# Sheet1.net
KiCad netlist of a schematic drawn in Altium Designer
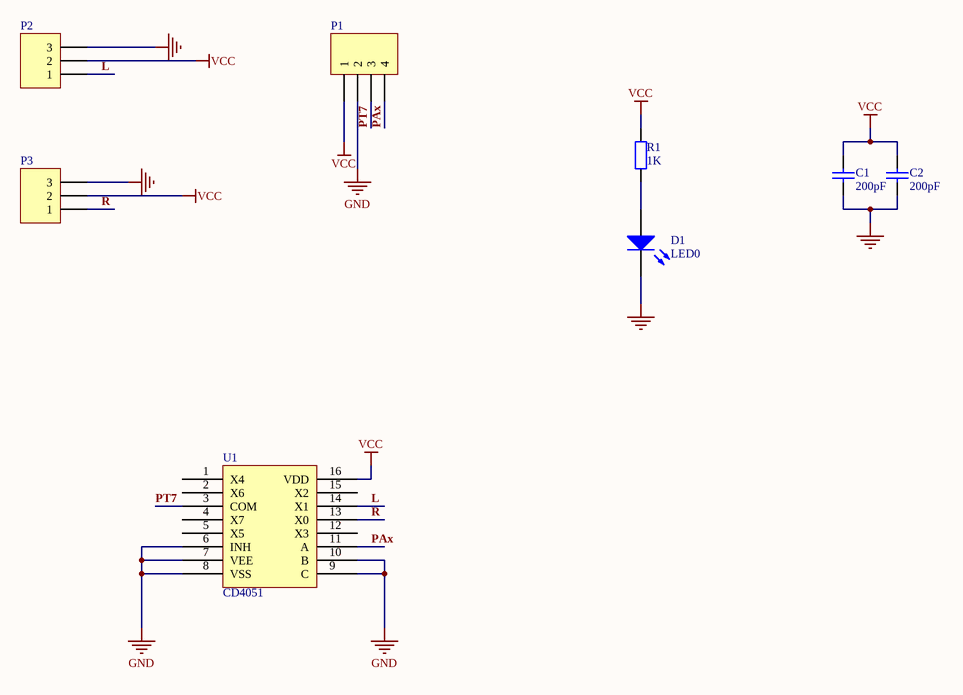
[diagram p0: Sheet1.SchDoc]

(export (version "E")
  (design (tool "Eeschema 10.0.6"))
  (components
    (comp (ref "C1")
      (value "200pF")
      (footprint "C0805")
      (description "Capacitor")
      (fields (field (name "Comment") "Cap") (field (name "PUBLISHER") "Altium Limited"))
      (libsource (lib "Miscellaneous Devices") (part "Cap"))
    )
    (comp (ref "C2")
      (value "200pF")
      (footprint "C0805")
      (description "Capacitor")
      (fields (field (name "Comment") "Cap") (field (name "PUBLISHER") "Altium Limited"))
      (libsource (lib "Miscellaneous Devices") (part "Cap"))
    )
    (comp (ref "D1")
      (value "LED0")
      (footprint "C0805")
      (description "Typical INFRARED GaAs LED")
      (fields (field (name "PUBLISHER") "Altium Limited"))
      (libsource (lib "Miscellaneous Devices") (part "LED0"))
    )
    (comp (ref "P1")
      (value "Header 4")
      (footprint "HDR1X4")
      (description "Header, 4-Pin")
      (fields (field (name "PUBLISHER") "Altium Limited"))
      (libsource (lib "Miscellaneous Connectors") (part "Header 4"))
    )
    (comp (ref "P2")
      (value "Header 3")
      (footprint "HDR1X3")
      (description "Header, 3-Pin")
      (fields (field (name "PUBLISHER") "Altium Limited"))
      (libsource (lib "Miscellaneous Connectors") (part "Header 3"))
    )
    (comp (ref "P3")
      (value "Header 3")
      (footprint "HDR1X3")
      (description "Header, 3-Pin")
      (fields (field (name "PUBLISHER") "Altium Limited"))
      (libsource (lib "Miscellaneous Connectors") (part "Header 3"))
    )
    (comp (ref "R1")
      (value "1K")
      (footprint "C0805")
      (description "Resistor")
      (fields (field (name "Comment") "Res2") (field (name "PUBLISHER") "Altium Limited"))
      (libsource (lib "Miscellaneous Devices") (part "Res2"))
    )
    (comp (ref "U1") (value "CD4051") (footprint "DIP-16") (libsource (lib "Schlib1") (part "Component_1")))
  )
  (nets
    (net (code "1") (name "/L") (class "Default")
      (node (ref "P2") (pin "1") (pinfunction "1_1") (pintype "passive"))
      (node (ref "U1") (pin "14") (pinfunction "X1_14") (pintype "passive"))
    )
    (net (code "2") (name "/PAx") (class "Default")
      (node (ref "P1") (pin "4") (pinfunction "4_4") (pintype "passive"))
      (node (ref "U1") (pin "11") (pinfunction "A_11") (pintype "passive"))
    )
    (net (code "3") (name "/PT7") (class "Default")
      (node (ref "P1") (pin "3") (pinfunction "3_3") (pintype "passive"))
      (node (ref "U1") (pin "3") (pinfunction "COM_3") (pintype "passive"))
    )
    (net (code "4") (name "/R") (class "Default")
      (node (ref "P3") (pin "1") (pinfunction "1_1") (pintype "passive"))
      (node (ref "U1") (pin "13") (pinfunction "X0_13") (pintype "passive"))
    )
    (net (code "5") (name "GND") (class "Default")
      (node (ref "C1") (pin "1") (pinfunction "1_1") (pintype "passive"))
      (node (ref "C2") (pin "1") (pinfunction "1_1") (pintype "passive"))
      (node (ref "D1") (pin "2") (pinfunction "K_2") (pintype "passive"))
      (node (ref "P1") (pin "2") (pinfunction "2_2") (pintype "passive"))
      (node (ref "P2") (pin "3") (pinfunction "3_3") (pintype "passive"))
      (node (ref "P3") (pin "3") (pinfunction "3_3") (pintype "passive"))
      (node (ref "U1") (pin "10") (pinfunction "B_10") (pintype "passive"))
      (node (ref "U1") (pin "6") (pinfunction "INH_6") (pintype "passive"))
      (node (ref "U1") (pin "7") (pinfunction "VEE_7") (pintype "passive"))
      (node (ref "U1") (pin "8") (pinfunction "VSS_8") (pintype "passive"))
      (node (ref "U1") (pin "9") (pinfunction "C_9") (pintype "passive"))
    )
    (net (code "6") (name "Net-(D1-A)") (class "Default")
      (node (ref "D1") (pin "1") (pinfunction "A_1") (pintype "passive"))
      (node (ref "R1") (pin "1") (pinfunction "1_1") (pintype "passive"))
    )
    (net (code "7") (name "VCC") (class "Default")
      (node (ref "C1") (pin "2") (pinfunction "2_2") (pintype "passive"))
      (node (ref "C2") (pin "2") (pinfunction "2_2") (pintype "passive"))
      (node (ref "P1") (pin "1") (pinfunction "1_1") (pintype "passive"))
      (node (ref "P2") (pin "2") (pinfunction "2_2") (pintype "passive"))
      (node (ref "P3") (pin "2") (pinfunction "2_2") (pintype "passive"))
      (node (ref "R1") (pin "2") (pinfunction "2_2") (pintype "passive"))
      (node (ref "U1") (pin "16") (pinfunction "VDD_16") (pintype "passive"))
    )
    (net (code "8") (name "unconnected-(U1-X2-Pad15)") (class "Default")
      (node (ref "U1") (pin "15") (pinfunction "X2_15") (pintype "passive"))
    )
    (net (code "9") (name "unconnected-(U1-X3-Pad12)") (class "Default")
      (node (ref "U1") (pin "12") (pinfunction "X3_12") (pintype "passive"))
    )
    (net (code "10") (name "unconnected-(U1-X4-Pad1)") (class "Default")
      (node (ref "U1") (pin "1") (pinfunction "X4_1") (pintype "passive"))
    )
    (net (code "11") (name "unconnected-(U1-X5-Pad5)") (class "Default")
      (node (ref "U1") (pin "5") (pinfunction "X5_5") (pintype "passive"))
    )
    (net (code "12") (name "unconnected-(U1-X6-Pad2)") (class "Default")
      (node (ref "U1") (pin "2") (pinfunction "X6_2") (pintype "passive"))
    )
    (net (code "13") (name "unconnected-(U1-X7-Pad4)") (class "Default")
      (node (ref "U1") (pin "4") (pinfunction "X7_4") (pintype "passive"))
    )
  )
)
